# OpenBook_EBookReader_Schematic.net
KiCad netlist of a schematic drawn in EAGLE
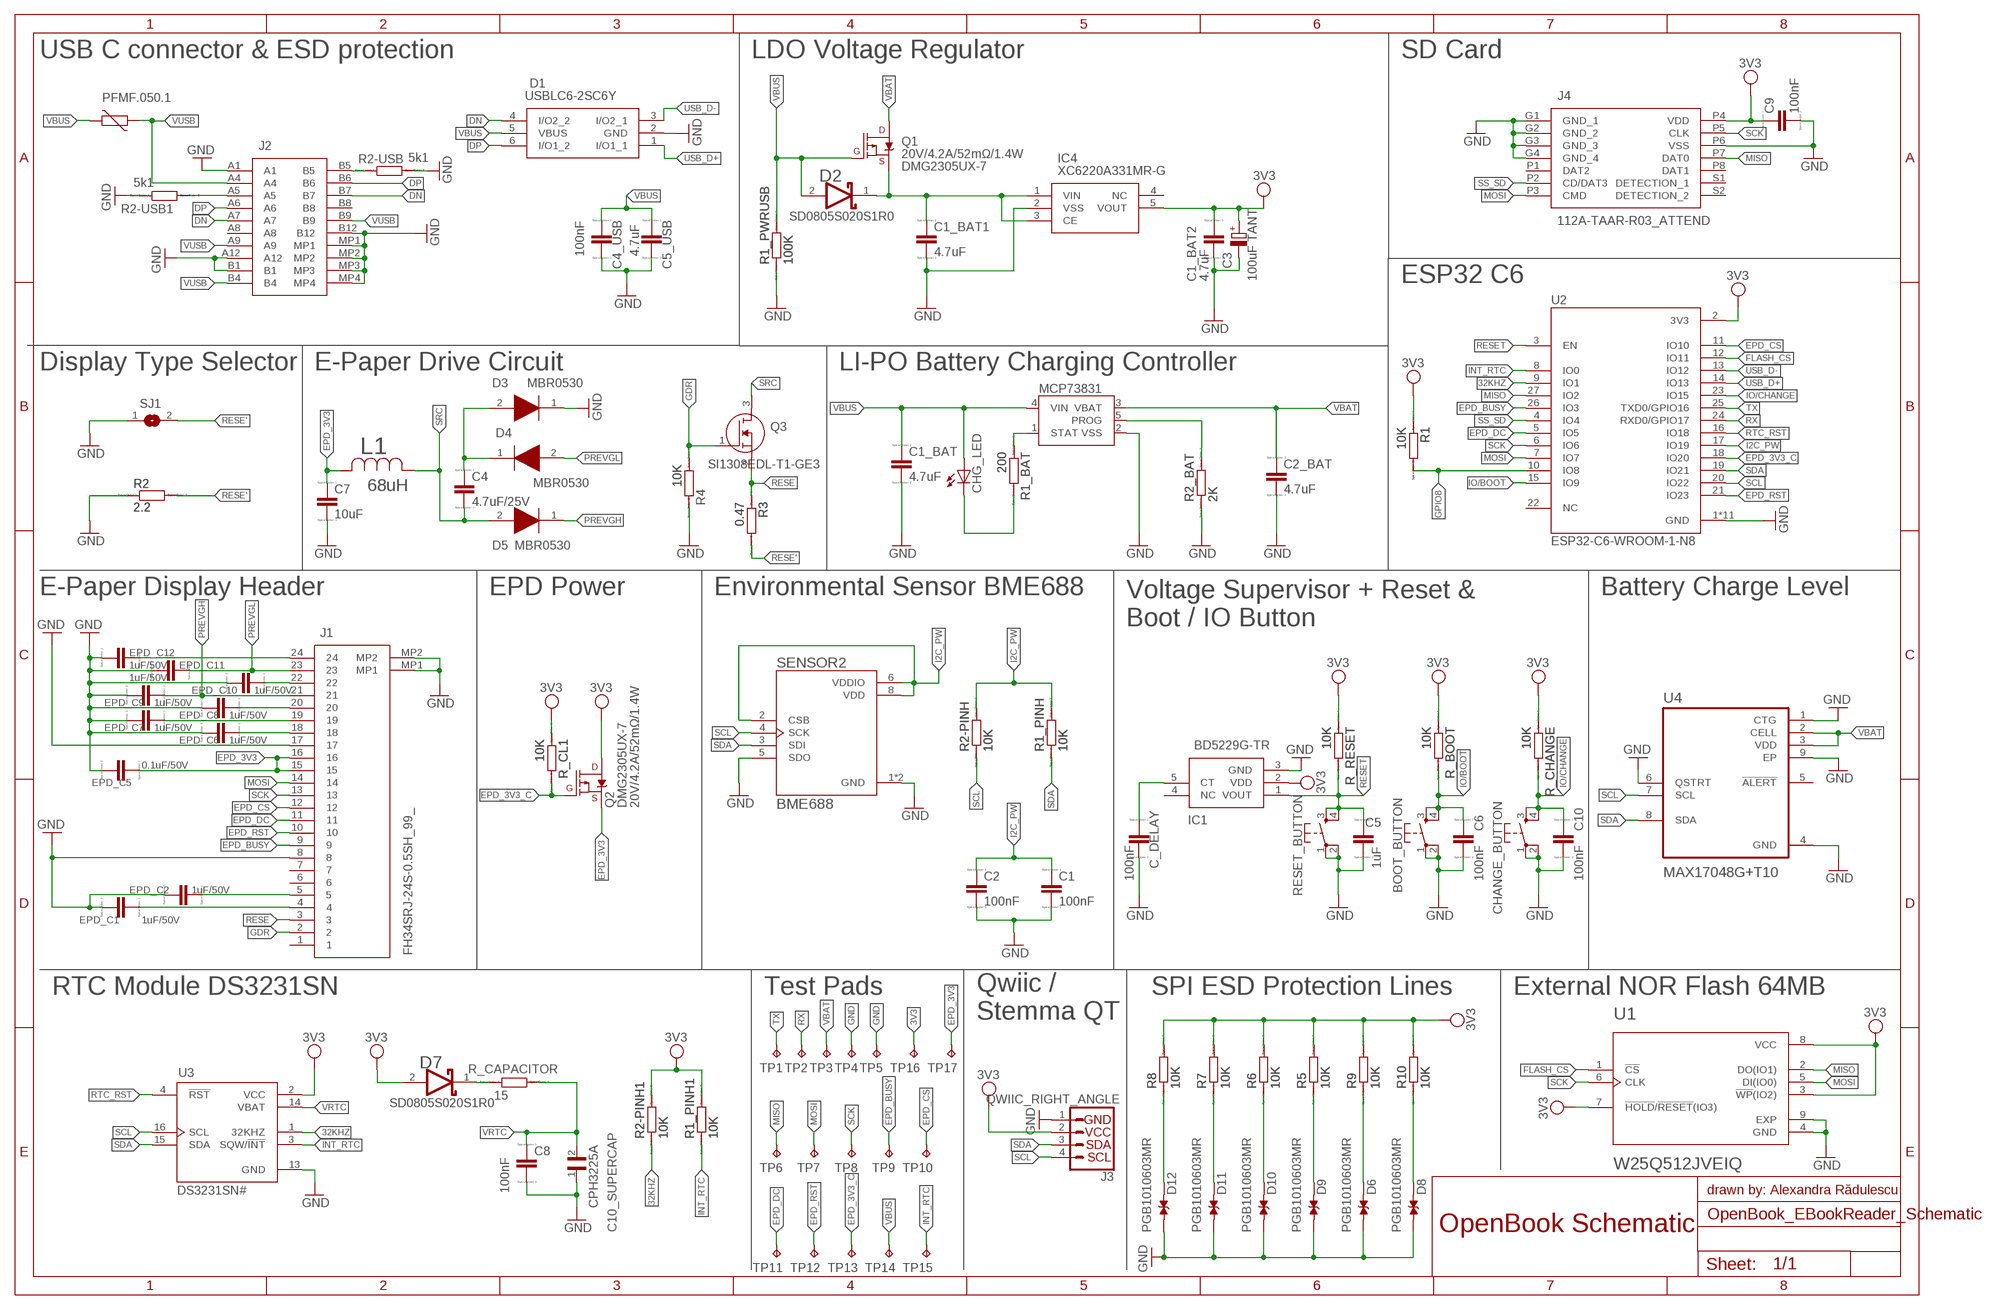
[diagram p0: schematic, sheet 1]

(export (version "E")
  (design (tool "Eeschema 10.0.6"))
  (components
    (comp (ref "BOOT_BUTTON")
      (value "BUTTON_CUSYOMV1")
      (footprint "eagle-import:MYBUTTON")
      (libsource (lib "eagle-import") (part "BUTTON_CUSYOMV1"))
    )
    (comp (ref "C1")
      (value "100nF")
      (footprint "eagle-import:ESP32_WROVER_EAGLE-LTSPICE_C0402")
      (libsource (lib "eagle-import") (part "ESP32_WROVER_EAGLE-LTSPICE_CC0402"))
    )
    (comp (ref "C1_BAT")
      (value "4.7uF")
      (footprint "eagle-import:ESP32_WROVER_EAGLE-LTSPICE_C0402")
      (libsource (lib "eagle-import") (part "ESP32_WROVER_EAGLE-LTSPICE_CC0402"))
    )
    (comp (ref "C1_BAT1")
      (value "4.7uF")
      (footprint "eagle-import:ESP32_WROVER_EAGLE-LTSPICE_C0402")
      (libsource (lib "eagle-import") (part "ESP32_WROVER_EAGLE-LTSPICE_CC0402"))
    )
    (comp (ref "C1_BAT2")
      (value "4.7uF")
      (footprint "eagle-import:ESP32_WROVER_EAGLE-LTSPICE_C0402")
      (libsource (lib "eagle-import") (part "ESP32_WROVER_EAGLE-LTSPICE_CC0402"))
    )
    (comp (ref "C2")
      (value "100nF")
      (footprint "eagle-import:ESP32_WROVER_EAGLE-LTSPICE_C0402")
      (libsource (lib "eagle-import") (part "ESP32_WROVER_EAGLE-LTSPICE_CC0402"))
    )
    (comp (ref "C2_BAT")
      (value "4.7uF")
      (footprint "eagle-import:ESP32_WROVER_EAGLE-LTSPICE_C0402")
      (libsource (lib "eagle-import") (part "ESP32_WROVER_EAGLE-LTSPICE_CC0402"))
    )
    (comp (ref "C3")
      (value "100uF TANT")
      (footprint "eagle-import:RCL_CT3528")
      (libsource (lib "eagle-import") (part "RCL_CPOL-EUCT3528"))
    )
    (comp (ref "C4")
      (value "4.7uF/25V")
      (footprint "eagle-import:ESP32_WROVER_EAGLE-LTSPICE_C0402")
      (libsource (lib "eagle-import") (part "ESP32_WROVER_EAGLE-LTSPICE_CC0402"))
    )
    (comp (ref "C4_USB")
      (value "100nF")
      (footprint "eagle-import:ESP32_WROVER_EAGLE-LTSPICE_C0402")
      (libsource (lib "eagle-import") (part "ESP32_WROVER_EAGLE-LTSPICE_CC0402"))
    )
    (comp (ref "C5")
      (value "1uF")
      (footprint "eagle-import:ESP32_WROVER_EAGLE-LTSPICE_C0402")
      (libsource (lib "eagle-import") (part "ESP32_WROVER_EAGLE-LTSPICE_CC0402"))
    )
    (comp (ref "C5_USB")
      (value "4.7uF")
      (footprint "eagle-import:ESP32_WROVER_EAGLE-LTSPICE_C0402")
      (libsource (lib "eagle-import") (part "ESP32_WROVER_EAGLE-LTSPICE_CC0402"))
    )
    (comp (ref "C6")
      (value "100nF")
      (footprint "eagle-import:ESP32_WROVER_EAGLE-LTSPICE_C0402")
      (libsource (lib "eagle-import") (part "ESP32_WROVER_EAGLE-LTSPICE_CC0402"))
    )
    (comp (ref "C7")
      (value "10uF")
      (footprint "eagle-import:ESP32_WROVER_EAGLE-LTSPICE_C0402")
      (libsource (lib "eagle-import") (part "ESP32_WROVER_EAGLE-LTSPICE_CC0402"))
    )
    (comp (ref "C8")
      (value "100nF")
      (footprint "eagle-import:ESP32_WROVER_EAGLE-LTSPICE_C0402")
      (libsource (lib "eagle-import") (part "ESP32_WROVER_EAGLE-LTSPICE_CC0402"))
    )
    (comp (ref "C9")
      (value "100nF")
      (footprint "eagle-import:ESP32_WROVER_EAGLE-LTSPICE_C0402")
      (libsource (lib "eagle-import") (part "ESP32_WROVER_EAGLE-LTSPICE_CC0402"))
    )
    (comp (ref "C10")
      (value "100nF")
      (footprint "eagle-import:ESP32_WROVER_EAGLE-LTSPICE_C0402")
      (libsource (lib "eagle-import") (part "ESP32_WROVER_EAGLE-LTSPICE_CC0402"))
    )
    (comp (ref "C10_SUPERCAP")
      (value "CPH3225A")
      (footprint "eagle-import:CAPCP3225X100N")
      (fields (field (name "MF") "Seiko Instruments"))
      (libsource (lib "eagle-import") (part "CPH3225A"))
    )
    (comp (ref "CHANGE_BUTTON")
      (value "BUTTON_CUSYOMV1")
      (footprint "eagle-import:MYBUTTON")
      (libsource (lib "eagle-import") (part "BUTTON_CUSYOMV1"))
    )
    (comp (ref "CHG_LED")
      (value "ADAFRUIT_LEDCHIP-LED0603")
      (footprint "eagle-import:ADAFRUIT_CHIP-LED0603")
      (libsource (lib "eagle-import") (part "ADAFRUIT_LEDCHIP-LED0603"))
    )
    (comp (ref "C_DELAY")
      (value "100nF")
      (footprint "eagle-import:ESP32_WROVER_EAGLE-LTSPICE_C0402")
      (libsource (lib "eagle-import") (part "ESP32_WROVER_EAGLE-LTSPICE_CC0402"))
    )
    (comp (ref "D1")
      (value "USBLC6-2SC6Y")
      (footprint "eagle-import:SOT95P280X145-6N")
      (fields (field (name "MF") "STMicroelectronics"))
      (libsource (lib "eagle-import") (part "USBLC6-2SC6Y"))
    )
    (comp (ref "D2")
      (value "ESP32_WROVER_AVX---SD0805S020S1R0_AVX_SD0805S020S1R0_0_0AVX_SD0805S020S1R0_0_0")
      (footprint "eagle-import:ESP32_WROVER_AVX---SD0805S020S1R0_AVX_SD0805S020S1R0_0")
      (fields
        (field (name "DIGIKEY_PART_NUMBER") "478-7800-1-ND")
        (field (name "MF") "AVX")
        (field (name "MOUSER_PART_NUMBER") "581-SD0805S020S1R0")
      )
      (libsource (lib "eagle-import") (part "ESP32_WROVER_AVX---SD0805S020S1R0_AVX_SD0805S020S1R0_0_0AVX_SD0805S020S1R0_0_0"))
    )
    (comp (ref "D3")
      (value "MBR0530")
      (footprint "eagle-import:SOD3716X135N")
      (fields (field (name "MF") "ON Semiconductor"))
      (libsource (lib "eagle-import") (part "MBR0530"))
    )
    (comp (ref "D4")
      (value "MBR0530")
      (footprint "eagle-import:SOD3716X135N")
      (fields (field (name "MF") "ON Semiconductor"))
      (libsource (lib "eagle-import") (part "MBR0530"))
    )
    (comp (ref "D5")
      (value "MBR0530")
      (footprint "eagle-import:SOD3716X135N")
      (fields (field (name "MF") "ON Semiconductor"))
      (libsource (lib "eagle-import") (part "MBR0530"))
    )
    (comp (ref "D6")
      (value "PGB1010603MR")
      (footprint "eagle-import:DIOC1608X36N")
      (fields (field (name "MF") "Littelfuse Inc."))
      (libsource (lib "eagle-import") (part "PGB1010603MR"))
    )
    (comp (ref "D7")
      (value "SD0805S020S1R0")
      (footprint "eagle-import:ESP32_WROVER_AVX---SD0805S020S1R0_AVX_SD0805S020S1R0_0")
      (fields
        (field (name "DIGIKEY_PART_NUMBER") "478-7800-1-ND")
        (field (name "MF") "AVX")
        (field (name "MOUSER_PART_NUMBER") "581-SD0805S020S1R0")
      )
      (libsource (lib "eagle-import") (part "ESP32_WROVER_AVX---SD0805S020S1R0_AVX_SD0805S020S1R0_0_0AVX_SD0805S020S1R0_0_0"))
    )
    (comp (ref "D8")
      (value "PGB1010603MR")
      (footprint "eagle-import:DIOC1608X36N")
      (fields (field (name "MF") "Littelfuse Inc."))
      (libsource (lib "eagle-import") (part "PGB1010603MR"))
    )
    (comp (ref "D9")
      (value "PGB1010603MR")
      (footprint "eagle-import:DIOC1608X36N")
      (fields (field (name "MF") "Littelfuse Inc."))
      (libsource (lib "eagle-import") (part "PGB1010603MR"))
    )
    (comp (ref "D10")
      (value "PGB1010603MR")
      (footprint "eagle-import:DIOC1608X36N")
      (fields (field (name "MF") "Littelfuse Inc."))
      (libsource (lib "eagle-import") (part "PGB1010603MR"))
    )
    (comp (ref "D11")
      (value "PGB1010603MR")
      (footprint "eagle-import:DIOC1608X36N")
      (fields (field (name "MF") "Littelfuse Inc."))
      (libsource (lib "eagle-import") (part "PGB1010603MR"))
    )
    (comp (ref "D12")
      (value "PGB1010603MR")
      (footprint "eagle-import:DIOC1608X36N")
      (fields (field (name "MF") "Littelfuse Inc."))
      (libsource (lib "eagle-import") (part "PGB1010603MR"))
    )
    (comp (ref "EPD_C1")
      (value "1uF/50V")
      (footprint "eagle-import:ESP32_WROVER_EAGLE-LTSPICE_C0402")
      (libsource (lib "eagle-import") (part "ESP32_WROVER_EAGLE-LTSPICE_CC0402"))
    )
    (comp (ref "EPD_C2")
      (value "1uF/50V")
      (footprint "eagle-import:ESP32_WROVER_EAGLE-LTSPICE_C0402")
      (libsource (lib "eagle-import") (part "ESP32_WROVER_EAGLE-LTSPICE_CC0402"))
    )
    (comp (ref "EPD_C5")
      (value "0.1uF/50V")
      (footprint "eagle-import:ESP32_WROVER_EAGLE-LTSPICE_C0402")
      (libsource (lib "eagle-import") (part "ESP32_WROVER_EAGLE-LTSPICE_CC0402"))
    )
    (comp (ref "EPD_C6")
      (value "1uF/50V")
      (footprint "eagle-import:ESP32_WROVER_EAGLE-LTSPICE_C0402")
      (libsource (lib "eagle-import") (part "ESP32_WROVER_EAGLE-LTSPICE_CC0402"))
    )
    (comp (ref "EPD_C7")
      (value "1uF/50V")
      (footprint "eagle-import:ESP32_WROVER_EAGLE-LTSPICE_C0402")
      (libsource (lib "eagle-import") (part "ESP32_WROVER_EAGLE-LTSPICE_CC0402"))
    )
    (comp (ref "EPD_C8")
      (value "1uF/50V")
      (footprint "eagle-import:ESP32_WROVER_EAGLE-LTSPICE_C0402")
      (libsource (lib "eagle-import") (part "ESP32_WROVER_EAGLE-LTSPICE_CC0402"))
    )
    (comp (ref "EPD_C9")
      (value "1uF/50V")
      (footprint "eagle-import:ESP32_WROVER_EAGLE-LTSPICE_C0402")
      (libsource (lib "eagle-import") (part "ESP32_WROVER_EAGLE-LTSPICE_CC0402"))
    )
    (comp (ref "EPD_C10")
      (value "1uF/50V")
      (footprint "eagle-import:ESP32_WROVER_EAGLE-LTSPICE_C0402")
      (libsource (lib "eagle-import") (part "ESP32_WROVER_EAGLE-LTSPICE_CC0402"))
    )
    (comp (ref "EPD_C11")
      (value "1uF/50V")
      (footprint "eagle-import:ESP32_WROVER_EAGLE-LTSPICE_C0402")
      (libsource (lib "eagle-import") (part "ESP32_WROVER_EAGLE-LTSPICE_CC0402"))
    )
    (comp (ref "EPD_C12")
      (value "1uF/50V")
      (footprint "eagle-import:ESP32_WROVER_EAGLE-LTSPICE_C0402")
      (libsource (lib "eagle-import") (part "ESP32_WROVER_EAGLE-LTSPICE_CC0402"))
    )
    (comp (ref "IC1")
      (value "BD5229G-TR")
      (footprint "eagle-import:SOT95P280X125-5N")
      (fields (field (name "MOUSER_PART_NUMBER") "755-BD5229G-TR"))
      (libsource (lib "eagle-import") (part "BD5229G-TR"))
    )
    (comp (ref "IC4")
      (value "XC6220A331MR-G")
      (footprint "eagle-import:SOT95P280X120-5N")
      (fields (field (name "MOUSER_PART_NUMBER") "865-XC6220A331MR-G"))
      (libsource (lib "eagle-import") (part "XC6220A331MR-G"))
    )
    (comp (ref "J1")
      (value "FH34SRJ-24S-0.5SH_99_")
      (footprint "eagle-import:FH34SRJ24S05SH99")
      (fields
        (field (name "MANUFACTURER_PART_NUMBER") "FH34SRJ-24S-0.5SH(99)")
        (field (name "MOUSER_PART_NUMBER") "798-FH34SRJ24S05SH99")
      )
      (libsource (lib "eagle-import") (part "FH34SRJ-24S-0.5SH_99_"))
    )
    (comp (ref "J2")
      (value "SAMACSYS_PARTS_USB4110-GF-A")
      (footprint "eagle-import:SAMACSYS_PARTS_USB4110GFA")
      (fields
        (field (name "MANUFACTURER_PART_NUMBER") "USB4110-GF-A")
        (field (name "MOUSER_PART_NUMBER") "640-USB4110-GF-A")
      )
      (libsource (lib "eagle-import") (part "SAMACSYS_PARTS_USB4110-GF-A"))
    )
    (comp (ref "J3")
      (value "QWIIC_RIGHT_ANGLE")
      (footprint "eagle-import:JST04_1MM_RA")
      (libsource (lib "eagle-import") (part "QWIIC_CONNECTORJS-1MM"))
    )
    (comp (ref "J4")
      (value "112A-TAAR-R03_ATTEND")
      (footprint "eagle-import:112ATAARR03ATTEND")
      (fields (field (name "MANUFACTURER_PART_NUMBER") "112A-TAAR-R03 ATTEND"))
      (libsource (lib "eagle-import") (part "112A-TAAR-R03_ATTEND"))
    )
    (comp (ref "L1")
      (value "68uH")
      (footprint "eagle-import:IND_4828-WE-TPC_WRE")
      (fields
        (field (name "MANUFACTURER_PART_NUMBER") "744043680")
        (field (name "COPYRIGHT") "Copyright (C) 2024 Ultra Librarian. All rights reserved.")
      )
      (libsource (lib "eagle-import") (part "744043680IND_4828-WE-TPC_WRE"))
    )
    (comp (ref "MCP73831")
      (value "ESP32_WROVER_SPARKFUN-IC-POWER_MCP73831")
      (footprint "eagle-import:ESP32_WROVER_SPARKFUN-IC-POWER_SOT23-5")
      (libsource (lib "eagle-import") (part "ESP32_WROVER_SPARKFUN-IC-POWER_MCP73831"))
    )
    (comp (ref "PFMF.050.1")
      (value "ESP32C6_VARISTORCN1812")
      (footprint "eagle-import:ESP32C6_VARISTOR_CT_CN1812")
      (libsource (lib "eagle-import") (part "ESP32C6_VARISTORCN1812"))
    )
    (comp (ref "Q1")
      (value "20V/4.2A/52mΩ/1.4W")
      (footprint "eagle-import:ESP32_WROVER_SPARKFUN-DISCRETESEMI_SOT23-3")
      (libsource (lib "eagle-import") (part "ESP32_WROVER_SPARKFUN-DISCRETESEMI_MOSFET_PCH-DMG2305UX-7"))
    )
    (comp (ref "Q2")
      (value "20V/4.2A/52mΩ/1.4W")
      (footprint "eagle-import:ESP32_WROVER_SPARKFUN-DISCRETESEMI_SOT23-3")
      (libsource (lib "eagle-import") (part "ESP32_WROVER_SPARKFUN-DISCRETESEMI_MOSFET_PCH-DMG2305UX-7"))
    )
    (comp (ref "Q3")
      (value "SI1308EDL-T1-GE3")
      (footprint "eagle-import:SOT65P210X110-3N")
      (fields (field (name "MF") "Vishay Siliconix"))
      (libsource (lib "eagle-import") (part "SI1308EDL-T1-GE3"))
    )
    (comp (ref "R1")
      (value "10K")
      (footprint "eagle-import:ESP32_WROVER_EAGLE-LTSPICE_R0402")
      (libsource (lib "eagle-import") (part "ESP32_WROVER_EAGLE-LTSPICE_RR0402"))
    )
    (comp (ref "R1_BAT")
      (value "200")
      (footprint "eagle-import:ESP32_WROVER_EAGLE-LTSPICE_R0402")
      (libsource (lib "eagle-import") (part "ESP32_WROVER_EAGLE-LTSPICE_RR0402"))
    )
    (comp (ref "R1_PINH")
      (value "10K")
      (footprint "eagle-import:ESP32_WROVER_EAGLE-LTSPICE_R0402")
      (libsource (lib "eagle-import") (part "ESP32_WROVER_EAGLE-LTSPICE_RR0402"))
    )
    (comp (ref "R1_PINH1")
      (value "10K")
      (footprint "eagle-import:ESP32_WROVER_EAGLE-LTSPICE_R0402")
      (libsource (lib "eagle-import") (part "ESP32_WROVER_EAGLE-LTSPICE_RR0402"))
    )
    (comp (ref "R1_PWRUSB")
      (value "100K")
      (footprint "eagle-import:ESP32_WROVER_EAGLE-LTSPICE_R0402")
      (libsource (lib "eagle-import") (part "ESP32_WROVER_EAGLE-LTSPICE_RR0402"))
    )
    (comp (ref "R2")
      (value "2.2")
      (footprint "eagle-import:ESP32_WROVER_EAGLE-LTSPICE_R0402")
      (libsource (lib "eagle-import") (part "ESP32_WROVER_EAGLE-LTSPICE_RR0402"))
    )
    (comp (ref "R2-PINH")
      (value "10K")
      (footprint "eagle-import:ESP32_WROVER_EAGLE-LTSPICE_R0402")
      (libsource (lib "eagle-import") (part "ESP32_WROVER_EAGLE-LTSPICE_RR0402"))
    )
    (comp (ref "R2-PINH1")
      (value "10K")
      (footprint "eagle-import:ESP32_WROVER_EAGLE-LTSPICE_R0402")
      (libsource (lib "eagle-import") (part "ESP32_WROVER_EAGLE-LTSPICE_RR0402"))
    )
    (comp (ref "R2-USB")
      (value "5k1")
      (footprint "eagle-import:ESP32_WROVER_EAGLE-LTSPICE_R0402")
      (libsource (lib "eagle-import") (part "ESP32_WROVER_EAGLE-LTSPICE_RR0402"))
    )
    (comp (ref "R2-USB1")
      (value "5k1")
      (footprint "eagle-import:ESP32_WROVER_EAGLE-LTSPICE_R0402")
      (libsource (lib "eagle-import") (part "ESP32_WROVER_EAGLE-LTSPICE_RR0402"))
    )
    (comp (ref "R2_BAT")
      (value "2K")
      (footprint "eagle-import:ESP32_WROVER_EAGLE-LTSPICE_R0402")
      (libsource (lib "eagle-import") (part "ESP32_WROVER_EAGLE-LTSPICE_RR0402"))
    )
    (comp (ref "R3")
      (value "0.47")
      (footprint "eagle-import:ESP32_WROVER_EAGLE-LTSPICE_R0402")
      (libsource (lib "eagle-import") (part "ESP32_WROVER_EAGLE-LTSPICE_RR0402"))
    )
    (comp (ref "R4")
      (value "10K")
      (footprint "eagle-import:ESP32_WROVER_EAGLE-LTSPICE_R0402")
      (libsource (lib "eagle-import") (part "ESP32_WROVER_EAGLE-LTSPICE_RR0402"))
    )
    (comp (ref "R5")
      (value "10K")
      (footprint "eagle-import:ESP32_WROVER_EAGLE-LTSPICE_R0402")
      (libsource (lib "eagle-import") (part "ESP32_WROVER_EAGLE-LTSPICE_RR0402"))
    )
    (comp (ref "R6")
      (value "10K")
      (footprint "eagle-import:ESP32_WROVER_EAGLE-LTSPICE_R0402")
      (libsource (lib "eagle-import") (part "ESP32_WROVER_EAGLE-LTSPICE_RR0402"))
    )
    (comp (ref "R7")
      (value "10K")
      (footprint "eagle-import:ESP32_WROVER_EAGLE-LTSPICE_R0402")
      (libsource (lib "eagle-import") (part "ESP32_WROVER_EAGLE-LTSPICE_RR0402"))
    )
    (comp (ref "R8")
      (value "10K")
      (footprint "eagle-import:ESP32_WROVER_EAGLE-LTSPICE_R0402")
      (libsource (lib "eagle-import") (part "ESP32_WROVER_EAGLE-LTSPICE_RR0402"))
    )
    (comp (ref "R9")
      (value "10K")
      (footprint "eagle-import:ESP32_WROVER_EAGLE-LTSPICE_R0402")
      (libsource (lib "eagle-import") (part "ESP32_WROVER_EAGLE-LTSPICE_RR0402"))
    )
    (comp (ref "R10")
      (value "10K")
      (footprint "eagle-import:ESP32_WROVER_EAGLE-LTSPICE_R0402")
      (libsource (lib "eagle-import") (part "ESP32_WROVER_EAGLE-LTSPICE_RR0402"))
    )
    (comp (ref "RESET_BUTTON")
      (value "BUTTON_CUSYOMV1")
      (footprint "eagle-import:MYBUTTON")
      (libsource (lib "eagle-import") (part "BUTTON_CUSYOMV1"))
    )
    (comp (ref "R_BOOT")
      (value "10K")
      (footprint "eagle-import:ESP32_WROVER_EAGLE-LTSPICE_R0402")
      (libsource (lib "eagle-import") (part "ESP32_WROVER_EAGLE-LTSPICE_RR0402"))
    )
    (comp (ref "R_CAPACITOR")
      (value "15")
      (footprint "eagle-import:ESP32_WROVER_EAGLE-LTSPICE_R0402")
      (libsource (lib "eagle-import") (part "ESP32_WROVER_EAGLE-LTSPICE_RR0402"))
    )
    (comp (ref "R_CHANGE")
      (value "10K")
      (footprint "eagle-import:ESP32_WROVER_EAGLE-LTSPICE_R0402")
      (libsource (lib "eagle-import") (part "ESP32_WROVER_EAGLE-LTSPICE_RR0402"))
    )
    (comp (ref "R_CL1")
      (value "10K")
      (footprint "eagle-import:ESP32_WROVER_EAGLE-LTSPICE_R0402")
      (libsource (lib "eagle-import") (part "ESP32_WROVER_EAGLE-LTSPICE_RR0402"))
    )
    (comp (ref "R_RESET")
      (value "10K")
      (footprint "eagle-import:ESP32_WROVER_EAGLE-LTSPICE_R0402")
      (libsource (lib "eagle-import") (part "ESP32_WROVER_EAGLE-LTSPICE_RR0402"))
    )
    (comp (ref "SENSOR2")
      (value "BME688")
      (footprint "eagle-import:ESP32_WROVER_BME680_PSON80P300X300X100-8N")
      (fields (field (name "MF") "Bosch Sensortec") (field (name "MP") "BME680"))
      (libsource (lib "eagle-import") (part "ESP32_WROVER_BME680_BME680"))
    )
    (comp (ref "SJ1") (value "SJ") (footprint "eagle-import:SJ") (libsource (lib "eagle-import") (part "SJ")))
    (comp (ref "TP1")
      (value "TPTP20R")
      (footprint "eagle-import:TP20R")
      (libsource (lib "eagle-import") (part "TPTP20R"))
    )
    (comp (ref "TP2")
      (value "TPTP20R")
      (footprint "eagle-import:TP20R")
      (libsource (lib "eagle-import") (part "TPTP20R"))
    )
    (comp (ref "TP3")
      (value "TPTP20R")
      (footprint "eagle-import:TP20R")
      (libsource (lib "eagle-import") (part "TPTP20R"))
    )
    (comp (ref "TP4")
      (value "TPTP20R")
      (footprint "eagle-import:TP20R")
      (libsource (lib "eagle-import") (part "TPTP20R"))
    )
    (comp (ref "TP5")
      (value "TPTP20R")
      (footprint "eagle-import:TP20R")
      (libsource (lib "eagle-import") (part "TPTP20R"))
    )
    (comp (ref "TP6")
      (value "TPTP20R")
      (footprint "eagle-import:TP20R")
      (libsource (lib "eagle-import") (part "TPTP20R"))
    )
    (comp (ref "TP7")
      (value "TPTP20R")
      (footprint "eagle-import:TP20R")
      (libsource (lib "eagle-import") (part "TPTP20R"))
    )
    (comp (ref "TP8")
      (value "TPTP20R")
      (footprint "eagle-import:TP20R")
      (libsource (lib "eagle-import") (part "TPTP20R"))
    )
    (comp (ref "TP9")
      (value "TPTP20R")
      (footprint "eagle-import:TP20R")
      (libsource (lib "eagle-import") (part "TPTP20R"))
    )
    (comp (ref "TP10")
      (value "TPTP20R")
      (footprint "eagle-import:TP20R")
      (libsource (lib "eagle-import") (part "TPTP20R"))
    )
    (comp (ref "TP11")
      (value "TPTP20R")
      (footprint "eagle-import:TP20R")
      (libsource (lib "eagle-import") (part "TPTP20R"))
    )
    (comp (ref "TP12")
      (value "TPTP20R")
      (footprint "eagle-import:TP20R")
      (libsource (lib "eagle-import") (part "TPTP20R"))
    )
    (comp (ref "TP13")
      (value "TPTP20R")
      (footprint "eagle-import:TP20R")
      (libsource (lib "eagle-import") (part "TPTP20R"))
    )
    (comp (ref "TP14")
      (value "TPTP20R")
      (footprint "eagle-import:TP20R")
      (libsource (lib "eagle-import") (part "TPTP20R"))
    )
    (comp (ref "TP15")
      (value "TPTP20R")
      (footprint "eagle-import:TP20R")
      (libsource (lib "eagle-import") (part "TPTP20R"))
    )
    (comp (ref "TP16")
      (value "TPTP20R")
      (footprint "eagle-import:TP20R")
      (libsource (lib "eagle-import") (part "TPTP20R"))
    )
    (comp (ref "TP17")
      (value "TPTP20R")
      (footprint "eagle-import:TP20R")
      (libsource (lib "eagle-import") (part "TPTP20R"))
    )
    (comp (ref "U1")
      (value "W25Q512JVEIQ")
      (footprint "eagle-import:SON127P600X800X80-9N")
      (fields (field (name "MF") "Winbond Electronics"))
      (libsource (lib "eagle-import") (part "W25Q512JVEIQ"))
    )
    (comp (ref "U2")
      (value "ESP32-C6-WROOM-1-N8")
      (footprint "eagle-import:XCVR_ESP32-C6-WROOM-1-N8")
      (fields (field (name "MF") "Espressif Systems"))
      (libsource (lib "eagle-import") (part "ESP32-C6-WROOM-1-N8"))
    )
    (comp (ref "U3")
      (value "DS3231SN#")
      (footprint "eagle-import:SOIC127P1032X265-16N")
      (fields (field (name "MF") "Analog Devices"))
      (libsource (lib "eagle-import") (part "DS3231SN#"))
    )
    (comp (ref "U4")
      (value "MAX17048G+T10")
      (footprint "eagle-import:SON50P200X200X80-9N")
      (fields (field (name "MF") "Analog Devices"))
      (libsource (lib "eagle-import") (part "MAX17048G+T10"))
    )
  )
  (nets
    (net (code "1") (name "3V3") (class "Default")
      (node (ref "C1_BAT2") (pin "1") (pinfunction "1_1") (pintype "passive"))
      (node (ref "C3") (pin "+") (pinfunction "+_+") (pintype "passive"))
      (node (ref "C9") (pin "1") (pinfunction "1_1") (pintype "passive"))
      (node (ref "D7") (pin "2") (pinfunction "ANODE_2") (pintype "bidirectional"))
      (node (ref "IC1") (pin "2") (pinfunction "VDD_2") (pintype "bidirectional"))
      (node (ref "IC4") (pin "5") (pinfunction "VOUT_5") (pintype "bidirectional"))
      (node (ref "J3") (pin "2") (pinfunction "2_2") (pintype "power_in"))
      (node (ref "J4") (pin "P4") (pinfunction "VDD_P4") (pintype "bidirectional"))
      (node (ref "Q2") (pin "3") (pinfunction "D_3") (pintype "bidirectional"))
      (node (ref "R1") (pin "1") (pinfunction "1_1") (pintype "passive"))
      (node (ref "R10") (pin "2") (pinfunction "2_2") (pintype "passive"))
      (node (ref "R1_PINH1") (pin "2") (pinfunction "2_2") (pintype "passive"))
      (node (ref "R2-PINH1") (pin "2") (pinfunction "2_2") (pintype "passive"))
      (node (ref "R5") (pin "2") (pinfunction "2_2") (pintype "passive"))
      (node (ref "R6") (pin "2") (pinfunction "2_2") (pintype "passive"))
      (node (ref "R7") (pin "2") (pinfunction "2_2") (pintype "passive"))
      (node (ref "R8") (pin "2") (pinfunction "2_2") (pintype "passive"))
      (node (ref "R9") (pin "2") (pinfunction "2_2") (pintype "passive"))
      (node (ref "R_BOOT") (pin "1") (pinfunction "1_1") (pintype "passive"))
      (node (ref "R_CHANGE") (pin "1") (pinfunction "1_1") (pintype "passive"))
      (node (ref "R_CL1") (pin "1") (pinfunction "1_1") (pintype "passive"))
      (node (ref "R_RESET") (pin "1") (pinfunction "1_1") (pintype "passive"))
      (node (ref "TP16") (pin "TP") (pinfunction "TP_TP") (pintype "input"))
      (node (ref "U1") (pin "3") (pinfunction "~{WP}(IO2)_3") (pintype "bidirectional"))
      (node (ref "U1") (pin "7") (pinfunction "~{HOLD}/~{RESET}(IO3)_7") (pintype "bidirectional"))
      (node (ref "U1") (pin "8") (pinfunction "VCC_8") (pintype "power_in"))
      (node (ref "U2") (pin "2") (pinfunction "3V3_2") (pintype "power_in"))
      (node (ref "U3") (pin "2") (pinfunction "VCC_2") (pintype "power_in"))
    )
    (net (code "2") (name "32KHZ") (class "Default")
      (node (ref "R2-PINH1") (pin "1") (pinfunction "1_1") (pintype "passive"))
      (node (ref "U2") (pin "9") (pinfunction "IO1_9") (pintype "bidirectional"))
      (node (ref "U3") (pin "1") (pinfunction "32KHZ_1") (pintype "output"))
    )
    (net (code "3") (name "DN") (class "Default")
      (node (ref "D1") (pin "4") (pinfunction "I/O2_2_4") (pintype "bidirectional"))
      (node (ref "J2") (pin "A7") (pinfunction "A7_A7") (pintype "bidirectional"))
      (node (ref "J2") (pin "B7") (pinfunction "B7_B7") (pintype "bidirectional"))
    )
    (net (code "4") (name "DP") (class "Default")
      (node (ref "D1") (pin "6") (pinfunction "I/O1_2_6") (pintype "bidirectional"))
      (node (ref "J2") (pin "A6") (pinfunction "A6_A6") (pintype "bidirectional"))
      (node (ref "J2") (pin "B6") (pinfunction "B6_B6") (pintype "bidirectional"))
    )
    (net (code "5") (name "EPD_3V3") (class "Default")
      (node (ref "C7") (pin "1") (pinfunction "1_1") (pintype "passive"))
      (node (ref "EPD_C5") (pin "1") (pinfunction "1_1") (pintype "passive"))
      (node (ref "J1") (pin "15") (pinfunction "15_15") (pintype "bidirectional"))
      (node (ref "J1") (pin "16") (pinfunction "16_16") (pintype "bidirectional"))
      (node (ref "L1") (pin "2") (pinfunction "2_2") (pintype "passive"))
      (node (ref "Q2") (pin "2") (pinfunction "S_2") (pintype "bidirectional"))
      (node (ref "TP17") (pin "TP") (pinfunction "TP_TP") (pintype "input"))
    )
    (net (code "6") (name "EPD_3V3_C") (class "Default")
      (node (ref "Q2") (pin "1") (pinfunction "G_1") (pintype "bidirectional"))
      (node (ref "R_CL1") (pin "2") (pinfunction "2_2") (pintype "passive"))
      (node (ref "TP13") (pin "TP") (pinfunction "TP_TP") (pintype "input"))
      (node (ref "U2") (pin "18") (pinfunction "IO20_18") (pintype "bidirectional"))
    )
    (net (code "7") (name "EPD_BUSY") (class "Default")
      (node (ref "J1") (pin "9") (pinfunction "9_9") (pintype "bidirectional"))
      (node (ref "TP9") (pin "TP") (pinfunction "TP_TP") (pintype "input"))
      (node (ref "U2") (pin "26") (pinfunction "IO3_26") (pintype "bidirectional"))
    )
    (net (code "8") (name "EPD_CS") (class "Default")
      (node (ref "J1") (pin "12") (pinfunction "12_12") (pintype "bidirectional"))
      (node (ref "TP10") (pin "TP") (pinfunction "TP_TP") (pintype "input"))
      (node (ref "U2") (pin "11") (pinfunction "IO10_11") (pintype "bidirectional"))
    )
    (net (code "9") (name "EPD_DC") (class "Default")
      (node (ref "J1") (pin "11") (pinfunction "11_11") (pintype "bidirectional"))
      (node (ref "TP11") (pin "TP") (pinfunction "TP_TP") (pintype "input"))
      (node (ref "U2") (pin "5") (pinfunction "IO5_5") (pintype "bidirectional"))
    )
    (net (code "10") (name "EPD_RST") (class "Default")
      (node (ref "J1") (pin "10") (pinfunction "10_10") (pintype "bidirectional"))
      (node (ref "TP12") (pin "TP") (pinfunction "TP_TP") (pintype "input"))
      (node (ref "U2") (pin "21") (pinfunction "IO23_21") (pintype "bidirectional"))
    )
    (net (code "11") (name "FLASH_CS") (class "Default")
      (node (ref "U1") (pin "1") (pinfunction "~{CS}_1") (pintype "input"))
      (node (ref "U2") (pin "12") (pinfunction "IO11_12") (pintype "bidirectional"))
    )
    (net (code "12") (name "GDR") (class "Default")
      (node (ref "J1") (pin "2") (pinfunction "2_2") (pintype "bidirectional"))
      (node (ref "Q3") (pin "1") (pinfunction "G_1") (pintype "bidirectional"))
      (node (ref "R4") (pin "1") (pinfunction "1_1") (pintype "passive"))
    )
    (net (code "13") (name "GND") (class "Default")
      (node (ref "BOOT_BUTTON") (pin "1") (pinfunction "1_1") (pintype "passive"))
      (node (ref "BOOT_BUTTON") (pin "2") (pinfunction "2_2") (pintype "passive"))
      (node (ref "C1") (pin "2") (pinfunction "2_2") (pintype "passive"))
      (node (ref "C10") (pin "2") (pinfunction "2_2") (pintype "passive"))
      (node (ref "C10_SUPERCAP") (pin "1") (pinfunction "1_1") (pintype "passive"))
      (node (ref "C1_BAT") (pin "2") (pinfunction "2_2") (pintype "passive"))
      (node (ref "C1_BAT1") (pin "2") (pinfunction "2_2") (pintype "passive"))
      (node (ref "C1_BAT2") (pin "2") (pinfunction "2_2") (pintype "passive"))
      (node (ref "C2") (pin "2") (pinfunction "2_2") (pintype "passive"))
      (node (ref "C2_BAT") (pin "2") (pinfunction "2_2") (pintype "passive"))
      (node (ref "C3") (pin "-") (pinfunction "-_-") (pintype "passive"))
      (node (ref "C4_USB") (pin "2") (pinfunction "2_2") (pintype "passive"))
      (node (ref "C5") (pin "2") (pinfunction "2_2") (pintype "passive"))
      (node (ref "C5_USB") (pin "2") (pinfunction "2_2") (pintype "passive"))
      (node (ref "C6") (pin "2") (pinfunction "2_2") (pintype "passive"))
      (node (ref "C7") (pin "2") (pinfunction "2_2") (pintype "passive"))
      (node (ref "C8") (pin "2") (pinfunction "2_2") (pintype "passive"))
      (node (ref "C9") (pin "2") (pinfunction "2_2") (pintype "passive"))
      (node (ref "CHANGE_BUTTON") (pin "1") (pinfunction "1_1") (pintype "passive"))
      (node (ref "CHANGE_BUTTON") (pin "2") (pinfunction "2_2") (pintype "passive"))
      (node (ref "C_DELAY") (pin "2") (pinfunction "2_2") (pintype "passive"))
      (node (ref "D1") (pin "2") (pinfunction "GND_2") (pintype "bidirectional"))
      (node (ref "D10") (pin "1") (pinfunction "1_1") (pintype "passive"))
      (node (ref "D11") (pin "1") (pinfunction "1_1") (pintype "passive"))
      (node (ref "D12") (pin "1") (pinfunction "1_1") (pintype "passive"))
      (node (ref "D3") (pin "1") (pinfunction "K_1") (pintype "bidirectional"))
      (node (ref "D6") (pin "1") (pinfunction "1_1") (pintype "passive"))
      (node (ref "D8") (pin "1") (pinfunction "1_1") (pintype "passive"))
      (node (ref "D9") (pin "1") (pinfunction "1_1") (pintype "passive"))
      (node (ref "EPD_C1") (pin "2") (pinfunction "2_2") (pintype "passive"))
      (node (ref "EPD_C10") (pin "2") (pinfunction "2_2") (pintype "passive"))
      (node (ref "EPD_C11") (pin "2") (pinfunction "2_2") (pintype "passive"))
      (node (ref "EPD_C12") (pin "2") (pinfunction "2_2") (pintype "passive"))
      (node (ref "EPD_C2") (pin "2") (pinfunction "2_2") (pintype "passive"))
      (node (ref "EPD_C5") (pin "2") (pinfunction "2_2") (pintype "passive"))
      (node (ref "EPD_C6") (pin "2") (pinfunction "2_2") (pintype "passive"))
      (node (ref "EPD_C7") (pin "2") (pinfunction "2_2") (pintype "passive"))
      (node (ref "EPD_C8") (pin "2") (pinfunction "2_2") (pintype "passive"))
      (node (ref "EPD_C9") (pin "2") (pinfunction "2_2") (pintype "passive"))
      (node (ref "IC1") (pin "3") (pinfunction "GND_3") (pintype "bidirectional"))
      (node (ref "IC4") (pin "2") (pinfunction "VSS_2") (pintype "bidirectional"))
      (node (ref "J1") (pin "17") (pinfunction "17_17") (pintype "bidirectional"))
      (node (ref "J1") (pin "8") (pinfunction "8_8") (pintype "bidirectional"))
      (node (ref "J1") (pin "MP1") (pinfunction "MP1_MP1") (pintype "bidirectional"))
      (node (ref "J1") (pin "MP2") (pinfunction "MP2_MP2") (pintype "bidirectional"))
      (node (ref "J2") (pin "A1") (pinfunction "A1_A1") (pintype "bidirectional"))
      (node (ref "J2") (pin "A12") (pinfunction "A12_A12") (pintype "bidirectional"))
      (node (ref "J2") (pin "B1") (pinfunction "B1_B1") (pintype "bidirectional"))
      (node (ref "J2") (pin "B12") (pinfunction "B12_B12") (pintype "bidirectional"))
      (node (ref "J2") (pin "MP1") (pinfunction "MP1_MP1") (pintype "bidirectional"))
      (node (ref "J2") (pin "MP2") (pinfunction "MP2_MP2") (pintype "bidirectional"))
      (node (ref "J2") (pin "MP3") (pinfunction "MP3_MP3") (pintype "bidirectional"))
      (node (ref "J2") (pin "MP4") (pinfunction "MP4_MP4") (pintype "bidirectional"))
      (node (ref "J3") (pin "1") (pinfunction "1_1") (pintype "power_in"))
      (node (ref "J4") (pin "G1") (pinfunction "GND_1_G1") (pintype "bidirectional"))
      (node (ref "J4") (pin "G2") (pinfunction "GND_2_G2") (pintype "bidirectional"))
      (node (ref "J4") (pin "G3") (pinfunction "GND_3_G3") (pintype "bidirectional"))
      (node (ref "J4") (pin "G4") (pinfunction "GND_4_G4") (pintype "bidirectional"))
      (node (ref "J4") (pin "P6") (pinfunction "VSS_P6") (pintype "bidirectional"))
      (node (ref "MCP73831") (pin "2") (pinfunction "VSS_2") (pintype "power_in"))
      (node (ref "R1_PWRUSB") (pin "1") (pinfunction "1_1") (pintype "passive"))
      (node (ref "R2") (pin "1") (pinfunction "1_1") (pintype "passive"))
      (node (ref "R2-USB") (pin "2") (pinfunction "2_2") (pintype "passive"))
      (node (ref "R2-USB1") (pin "1") (pinfunction "1_1") (pintype "passive"))
      (node (ref "R2_BAT") (pin "1") (pinfunction "1_1") (pintype "passive"))
      (node (ref "R4") (pin "2") (pinfunction "2_2") (pintype "passive"))
      (node (ref "RESET_BUTTON") (pin "1") (pinfunction "1_1") (pintype "passive"))
      (node (ref "RESET_BUTTON") (pin "2") (pinfunction "2_2") (pintype "passive"))
      (node (ref "SENSOR2") (pin "1") (pinfunction "GND_1") (pintype "power_in"))
      (node (ref "SENSOR2") (pin "5") (pinfunction "SDO_5") (pintype "bidirectional"))
      (node (ref "SENSOR2") (pin "7") (pinfunction "GND_7") (pintype "power_in"))
      (node (ref "SJ1") (pin "1") (pinfunction "1_1") (pintype "passive"))
      (node (ref "TP4") (pin "TP") (pinfunction "TP_TP") (pintype "input"))
      (node (ref "TP5") (pin "TP") (pinfunction "TP_TP") (pintype "input"))
      (node (ref "U1") (pin "4") (pinfunction "GND_4") (pintype "power_in"))
      (node (ref "U1") (pin "9") (pinfunction "EXP_9") (pintype "passive"))
      (node (ref "U2") (pin "1") (pinfunction "GND_1") (pintype "power_in"))
      (node (ref "U2") (pin "28") (pinfunction "GND_28") (pintype "power_in"))
      (node (ref "U2") (pin "29_1") (pinfunction "GND_29_1") (pintype "power_in"))
      (node (ref "U2") (pin "29_2") (pinfunction "GND_29_2") (pintype "power_in"))
      (node (ref "U2") (pin "29_3") (pinfunction "GND_29_3") (pintype "power_in"))
      (node (ref "U2") (pin "29_4") (pinfunction "GND_29_4") (pintype "power_in"))
      (node (ref "U2") (pin "29_5") (pinfunction "GND_29_5") (pintype "power_in"))
      (node (ref "U2") (pin "29_6") (pinfunction "GND_29_6") (pintype "power_in"))
      (node (ref "U2") (pin "29_7") (pinfunction "GND_29_7") (pintype "power_in"))
      (node (ref "U2") (pin "29_8") (pinfunction "GND_29_8") (pintype "power_in"))
      (node (ref "U2") (pin "29_9") (pinfunction "GND_29_9") (pintype "power_in"))
      (node (ref "U3") (pin "13") (pinfunction "GND_13") (pintype "power_in"))
      (node (ref "U4") (pin "1") (pinfunction "CTG_1") (pintype "power_in"))
      (node (ref "U4") (pin "4") (pinfunction "GND_4") (pintype "power_in"))
      (node (ref "U4") (pin "6") (pinfunction "QSTRT_6") (pintype "input"))
      (node (ref "U4") (pin "9") (pinfunction "EP_9") (pintype "power_in"))
    )
    (net (code "14") (name "GPIO8") (class "Default")
      (node (ref "R1") (pin "2") (pinfunction "2_2") (pintype "passive"))
      (node (ref "U2") (pin "10") (pinfunction "IO8_10") (pintype "bidirectional"))
    )
    (net (code "15") (name "I2C_PW") (class "Default")
      (node (ref "C1") (pin "1") (pinfunction "1_1") (pintype "passive"))
      (node (ref "C2") (pin "1") (pinfunction "1_1") (pintype "passive"))
      (node (ref "R1_PINH") (pin "2") (pinfunction "2_2") (pintype "passive"))
      (node (ref "R2-PINH") (pin "2") (pinfunction "2_2") (pintype "passive"))
      (node (ref "SENSOR2") (pin "2") (pinfunction "CSB_2") (pintype "input"))
      (node (ref "SENSOR2") (pin "6") (pinfunction "VDDIO_6") (pintype "power_in"))
      (node (ref "SENSOR2") (pin "8") (pinfunction "VDD_8") (pintype "power_in"))
      (node (ref "U2") (pin "17") (pinfunction "IO19_17") (pintype "bidirectional"))
    )
    (net (code "16") (name "INT_RTC") (class "Default")
      (node (ref "R1_PINH1") (pin "1") (pinfunction "1_1") (pintype "passive"))
      (node (ref "TP15") (pin "TP") (pinfunction "TP_TP") (pintype "input"))
      (node (ref "U2") (pin "8") (pinfunction "IO0_8") (pintype "bidirectional"))
      (node (ref "U3") (pin "3") (pinfunction "SQW/~{INT}_3") (pintype "output"))
    )
    (net (code "17") (name "IO{slash}BOOT") (class "Default")
      (node (ref "BOOT_BUTTON") (pin "3") (pinfunction "3_3") (pintype "passive"))
      (node (ref "BOOT_BUTTON") (pin "4") (pinfunction "4_4") (pintype "passive"))
      (node (ref "C6") (pin "1") (pinfunction "1_1") (pintype "passive"))
      (node (ref "R_BOOT") (pin "2") (pinfunction "2_2") (pintype "passive"))
      (node (ref "U2") (pin "15") (pinfunction "IO9_15") (pintype "bidirectional"))
    )
    (net (code "18") (name "IO{slash}CHANGE") (class "Default")
      (node (ref "C10") (pin "1") (pinfunction "1_1") (pintype "passive"))
      (node (ref "CHANGE_BUTTON") (pin "3") (pinfunction "3_3") (pintype "passive"))
      (node (ref "CHANGE_BUTTON") (pin "4") (pinfunction "4_4") (pintype "passive"))
      (node (ref "R_CHANGE") (pin "2") (pinfunction "2_2") (pintype "passive"))
      (node (ref "U2") (pin "23") (pinfunction "IO15_23") (pintype "bidirectional"))
    )
    (net (code "19") (name "MISO") (class "Default")
      (node (ref "J4") (pin "P7") (pinfunction "DAT0_P7") (pintype "bidirectional"))
      (node (ref "TP6") (pin "TP") (pinfunction "TP_TP") (pintype "input"))
      (node (ref "U1") (pin "2") (pinfunction "DO(IO1)_2") (pintype "bidirectional"))
      (node (ref "U2") (pin "27") (pinfunction "IO2_27") (pintype "bidirectional"))
    )
    (net (code "20") (name "MOSI") (class "Default")
      (node (ref "J1") (pin "14") (pinfunction "14_14") (pintype "bidirectional"))
      (node (ref "J4") (pin "P3") (pinfunction "CMD_P3") (pintype "bidirectional"))
      (node (ref "TP7") (pin "TP") (pinfunction "TP_TP") (pintype "input"))
      (node (ref "U1") (pin "5") (pinfunction "DI(IO0)_5") (pintype "bidirectional"))
      (node (ref "U2") (pin "7") (pinfunction "IO7_7") (pintype "bidirectional"))
    )
    (net (code "21") (name "Net-(CHG_LED-PadC)") (class "Default")
      (node (ref "CHG_LED") (pin "C") (pinfunction "C_C") (pintype "passive"))
      (node (ref "R1_BAT") (pin "2") (pinfunction "2_2") (pintype "passive"))
    )
    (net (code "22") (name "Net-(D2-CATHODE)") (class "Default")
      (node (ref "C1_BAT1") (pin "1") (pinfunction "1_1") (pintype "passive"))
      (node (ref "D2") (pin "1") (pinfunction "CATHODE_1") (pintype "bidirectional"))
      (node (ref "IC4") (pin "1") (pinfunction "VIN_1") (pintype "bidirectional"))
      (node (ref "IC4") (pin "3") (pinfunction "CE_3") (pintype "bidirectional"))
      (node (ref "Q1") (pin "2") (pinfunction "S_2") (pintype "bidirectional"))
    )
    (net (code "23") (name "Net-(D3-A)") (class "Default")
      (node (ref "C4") (pin "1") (pinfunction "1_1") (pintype "passive"))
      (node (ref "D3") (pin "2") (pinfunction "A_2") (pintype "bidirectional"))
      (node (ref "D4") (pin "1") (pinfunction "K_1") (pintype "bidirectional"))
    )
    (net (code "24") (name "Net-(D6-Pad2)") (class "Default")
      (node (ref "D6") (pin "2") (pinfunction "2_2") (pintype "passive"))
      (node (ref "R9") (pin "1") (pinfunction "1_1") (pintype "passive"))
    )
    (net (code "25") (name "Net-(D7-CATHODE)") (class "Default")
      (node (ref "D7") (pin "1") (pinfunction "CATHODE_1") (pintype "bidirectional"))
      (node (ref "R_CAPACITOR") (pin "2") (pinfunction "2_2") (pintype "passive"))
    )
    (net (code "26") (name "Net-(D8-Pad2)") (class "Default")
      (node (ref "D8") (pin "2") (pinfunction "2_2") (pintype "passive"))
      (node (ref "R10") (pin "1") (pinfunction "1_1") (pintype "passive"))
    )
    (net (code "27") (name "Net-(D9-Pad2)") (class "Default")
      (node (ref "D9") (pin "2") (pinfunction "2_2") (pintype "passive"))
      (node (ref "R5") (pin "1") (pinfunction "1_1") (pintype "passive"))
    )
    (net (code "28") (name "Net-(D10-Pad2)") (class "Default")
      (node (ref "D10") (pin "2") (pinfunction "2_2") (pintype "passive"))
      (node (ref "R6") (pin "1") (pinfunction "1_1") (pintype "passive"))
    )
    (net (code "29") (name "Net-(D11-Pad2)") (class "Default")
      (node (ref "D11") (pin "2") (pinfunction "2_2") (pintype "passive"))
      (node (ref "R7") (pin "1") (pinfunction "1_1") (pintype "passive"))
    )
    (net (code "30") (name "Net-(D12-Pad2)") (class "Default")
      (node (ref "D12") (pin "2") (pinfunction "2_2") (pintype "passive"))
      (node (ref "R8") (pin "1") (pinfunction "1_1") (pintype "passive"))
    )
    (net (code "31") (name "Net-(EPD_C1-Pad1)") (class "Default")
      (node (ref "EPD_C1") (pin "1") (pinfunction "1_1") (pintype "passive"))
      (node (ref "J1") (pin "4") (pinfunction "4_4") (pintype "bidirectional"))
    )
    (net (code "32") (name "Net-(EPD_C2-Pad1)") (class "Default")
      (node (ref "EPD_C2") (pin "1") (pinfunction "1_1") (pintype "passive"))
      (node (ref "J1") (pin "5") (pinfunction "5_5") (pintype "bidirectional"))
    )
    (net (code "33") (name "Net-(EPD_C6-Pad1)") (class "Default")
      (node (ref "EPD_C6") (pin "1") (pinfunction "1_1") (pintype "passive"))
      (node (ref "J1") (pin "18") (pinfunction "18_18") (pintype "bidirectional"))
    )
    (net (code "34") (name "Net-(EPD_C7-Pad1)") (class "Default")
      (node (ref "EPD_C7") (pin "1") (pinfunction "1_1") (pintype "passive"))
      (node (ref "J1") (pin "19") (pinfunction "19_19") (pintype "bidirectional"))
    )
    (net (code "35") (name "Net-(EPD_C8-Pad1)") (class "Default")
      (node (ref "EPD_C8") (pin "1") (pinfunction "1_1") (pintype "passive"))
      (node (ref "J1") (pin "20") (pinfunction "20_20") (pintype "bidirectional"))
    )
    (net (code "36") (name "Net-(EPD_C10-Pad1)") (class "Default")
      (node (ref "EPD_C10") (pin "1") (pinfunction "1_1") (pintype "passive"))
      (node (ref "J1") (pin "22") (pinfunction "22_22") (pintype "bidirectional"))
    )
    (net (code "37") (name "Net-(EPD_C12-Pad1)") (class "Default")
      (node (ref "EPD_C12") (pin "1") (pinfunction "1_1") (pintype "passive"))
      (node (ref "J1") (pin "24") (pinfunction "24_24") (pintype "bidirectional"))
    )
    (net (code "38") (name "Net-(IC1-CT)") (class "Default")
      (node (ref "C_DELAY") (pin "1") (pinfunction "1_1") (pintype "passive"))
      (node (ref "IC1") (pin "5") (pinfunction "CT_5") (pintype "bidirectional"))
    )
    (net (code "39") (name "Net-(J2-PadA5)") (class "Default")
      (node (ref "J2") (pin "A5") (pinfunction "A5_A5") (pintype "bidirectional"))
      (node (ref "R2-USB1") (pin "2") (pinfunction "2_2") (pintype "passive"))
    )
    (net (code "40") (name "Net-(J2-PadB5)") (class "Default")
      (node (ref "J2") (pin "B5") (pinfunction "B5_B5") (pintype "bidirectional"))
      (node (ref "R2-USB") (pin "1") (pinfunction "1_1") (pintype "passive"))
    )
    (net (code "41") (name "Net-(MCP73831-PROG)") (class "Default")
      (node (ref "MCP73831") (pin "5") (pinfunction "PROG_5") (pintype "input"))
      (node (ref "R2_BAT") (pin "2") (pinfunction "2_2") (pintype "passive"))
    )
    (net (code "42") (name "Net-(MCP73831-STAT)") (class "Default")
      (node (ref "MCP73831") (pin "1") (pinfunction "STAT_1") (pintype "output"))
      (node (ref "R1_BAT") (pin "1") (pinfunction "1_1") (pintype "passive"))
    )
    (net (code "43") (name "PREVGH") (class "Default")
      (node (ref "D5") (pin "1") (pinfunction "K_1") (pintype "bidirectional"))
      (node (ref "EPD_C9") (pin "1") (pinfunction "1_1") (pintype "passive"))
      (node (ref "J1") (pin "21") (pinfunction "21_21") (pintype "bidirectional"))
    )
    (net (code "44") (name "PREVGL") (class "Default")
      (node (ref "D4") (pin "2") (pinfunction "A_2") (pintype "bidirectional"))
      (node (ref "EPD_C11") (pin "1") (pinfunction "1_1") (pintype "passive"))
      (node (ref "J1") (pin "23") (pinfunction "23_23") (pintype "bidirectional"))
    )
    (net (code "45") (name "RESE") (class "Default")
      (node (ref "J1") (pin "3") (pinfunction "3_3") (pintype "bidirectional"))
      (node (ref "Q3") (pin "2") (pinfunction "S_2") (pintype "bidirectional"))
      (node (ref "R3") (pin "1") (pinfunction "1_1") (pintype "passive"))
    )
    (net (code "46") (name "RESE'") (class "Default")
      (node (ref "R2") (pin "2") (pinfunction "2_2") (pintype "passive"))
      (node (ref "R3") (pin "2") (pinfunction "2_2") (pintype "passive"))
      (node (ref "SJ1") (pin "2") (pinfunction "2_2") (pintype "passive"))
    )
    (net (code "47") (name "RESET") (class "Default")
      (node (ref "C5") (pin "1") (pinfunction "1_1") (pintype "passive"))
      (node (ref "IC1") (pin "1") (pinfunction "VOUT_1") (pintype "bidirectional"))
      (node (ref "RESET_BUTTON") (pin "3") (pinfunction "3_3") (pintype "passive"))
      (node (ref "RESET_BUTTON") (pin "4") (pinfunction "4_4") (pintype "passive"))
      (node (ref "R_RESET") (pin "2") (pinfunction "2_2") (pintype "passive"))
      (node (ref "U2") (pin "3") (pinfunction "EN_3") (pintype "input"))
    )
    (net (code "48") (name "RTC_RST") (class "Default")
      (node (ref "U2") (pin "16") (pinfunction "IO18_16") (pintype "bidirectional"))
      (node (ref "U3") (pin "4") (pinfunction "~{RST}_4") (pintype "input"))
    )
    (net (code "49") (name "RX") (class "Default")
      (node (ref "TP2") (pin "TP") (pinfunction "TP_TP") (pintype "input"))
      (node (ref "U2") (pin "24") (pinfunction "RXD0/GPIO17_24") (pintype "bidirectional"))
    )
    (net (code "50") (name "SCK") (class "Default")
      (node (ref "J1") (pin "13") (pinfunction "13_13") (pintype "bidirectional"))
      (node (ref "J4") (pin "P5") (pinfunction "CLK_P5") (pintype "bidirectional"))
      (node (ref "TP8") (pin "TP") (pinfunction "TP_TP") (pintype "input"))
      (node (ref "U1") (pin "6") (pinfunction "CLK_6") (pintype "input"))
      (node (ref "U2") (pin "6") (pinfunction "IO6_6") (pintype "bidirectional"))
    )
    (net (code "51") (name "SCL") (class "Default")
      (node (ref "J3") (pin "4") (pinfunction "4_4") (pintype "passive"))
      (node (ref "R2-PINH") (pin "1") (pinfunction "1_1") (pintype "passive"))
      (node (ref "SENSOR2") (pin "4") (pinfunction "SCK_4") (pintype "input"))
      (node (ref "U2") (pin "20") (pinfunction "IO22_20") (pintype "bidirectional"))
      (node (ref "U3") (pin "16") (pinfunction "SCL_16") (pintype "input"))
      (node (ref "U4") (pin "7") (pinfunction "SCL_7") (pintype "input"))
    )
    (net (code "52") (name "SDA") (class "Default")
      (node (ref "J3") (pin "3") (pinfunction "3_3") (pintype "passive"))
      (node (ref "R1_PINH") (pin "1") (pinfunction "1_1") (pintype "passive"))
      (node (ref "SENSOR2") (pin "3") (pinfunction "SDI_3") (pintype "bidirectional"))
      (node (ref "U2") (pin "19") (pinfunction "IO21_19") (pintype "bidirectional"))
      (node (ref "U3") (pin "15") (pinfunction "SDA_15") (pintype "bidirectional"))
      (node (ref "U4") (pin "8") (pinfunction "SDA_8") (pintype "bidirectional"))
    )
    (net (code "53") (name "SRC") (class "Default")
      (node (ref "C4") (pin "2") (pinfunction "2_2") (pintype "passive"))
      (node (ref "D5") (pin "2") (pinfunction "A_2") (pintype "bidirectional"))
      (node (ref "L1") (pin "1") (pinfunction "1_1") (pintype "passive"))
      (node (ref "Q3") (pin "3") (pinfunction "D_3") (pintype "bidirectional"))
    )
    (net (code "54") (name "SS_SD") (class "Default")
      (node (ref "J4") (pin "P2") (pinfunction "CD/DAT3_P2") (pintype "bidirectional"))
      (node (ref "U2") (pin "4") (pinfunction "IO4_4") (pintype "bidirectional"))
    )
    (net (code "55") (name "TX") (class "Default")
      (node (ref "TP1") (pin "TP") (pinfunction "TP_TP") (pintype "input"))
      (node (ref "U2") (pin "25") (pinfunction "TXD0/GPIO16_25") (pintype "bidirectional"))
    )
    (net (code "56") (name "USB_D+") (class "Default")
      (node (ref "D1") (pin "1") (pinfunction "I/O1_1_1") (pintype "bidirectional"))
      (node (ref "U2") (pin "14") (pinfunction "IO13_14") (pintype "bidirectional"))
    )
    (net (code "57") (name "USB_D-") (class "Default")
      (node (ref "D1") (pin "3") (pinfunction "I/O2_1_3") (pintype "bidirectional"))
      (node (ref "U2") (pin "13") (pinfunction "IO12_13") (pintype "bidirectional"))
    )
    (net (code "58") (name "VBAT") (class "Default")
      (node (ref "C2_BAT") (pin "1") (pinfunction "1_1") (pintype "passive"))
      (node (ref "MCP73831") (pin "3") (pinfunction "VBAT_3") (pintype "power_in"))
      (node (ref "Q1") (pin "3") (pinfunction "D_3") (pintype "bidirectional"))
      (node (ref "TP3") (pin "TP") (pinfunction "TP_TP") (pintype "input"))
      (node (ref "U4") (pin "2") (pinfunction "CELL_2") (pintype "power_in"))
      (node (ref "U4") (pin "3") (pinfunction "VDD_3") (pintype "power_in"))
    )
    (net (code "59") (name "VBUS") (class "Default")
      (node (ref "C1_BAT") (pin "1") (pinfunction "1_1") (pintype "passive"))
      (node (ref "C4_USB") (pin "1") (pinfunction "1_1") (pintype "passive"))
      (node (ref "C5_USB") (pin "1") (pinfunction "1_1") (pintype "passive"))
      (node (ref "CHG_LED") (pin "A") (pinfunction "A_A") (pintype "passive"))
      (node (ref "D1") (pin "5") (pinfunction "VBUS_5") (pintype "bidirectional"))
      (node (ref "D2") (pin "2") (pinfunction "ANODE_2") (pintype "bidirectional"))
      (node (ref "MCP73831") (pin "4") (pinfunction "VIN_4") (pintype "power_in"))
      (node (ref "PFMF.050.1") (pin "2") (pinfunction "2_2") (pintype "passive"))
      (node (ref "Q1") (pin "1") (pinfunction "G_1") (pintype "bidirectional"))
      (node (ref "R1_PWRUSB") (pin "2") (pinfunction "2_2") (pintype "passive"))
      (node (ref "TP14") (pin "TP") (pinfunction "TP_TP") (pintype "input"))
    )
    (net (code "60") (name "VRTC") (class "Default")
      (node (ref "C10_SUPERCAP") (pin "2") (pinfunction "2_2") (pintype "passive"))
      (node (ref "C8") (pin "1") (pinfunction "1_1") (pintype "passive"))
      (node (ref "R_CAPACITOR") (pin "1") (pinfunction "1_1") (pintype "passive"))
      (node (ref "U3") (pin "14") (pinfunction "VBAT_14") (pintype "power_in"))
    )
    (net (code "61") (name "VUSB") (class "Default")
      (node (ref "J2") (pin "A4") (pinfunction "A4_A4") (pintype "bidirectional"))
      (node (ref "J2") (pin "A9") (pinfunction "A9_A9") (pintype "bidirectional"))
      (node (ref "J2") (pin "B4") (pinfunction "B4_B4") (pintype "bidirectional"))
      (node (ref "J2") (pin "B9") (pinfunction "B9_B9") (pintype "bidirectional"))
      (node (ref "PFMF.050.1") (pin "1") (pinfunction "1_1") (pintype "passive"))
    )
    (net (code "62") (name "unconnected-(IC1-NC-Pad4)") (class "Default")
      (node (ref "IC1") (pin "4") (pinfunction "NC_4") (pintype "no_connect"))
    )
    (net (code "63") (name "unconnected-(IC4-NC-Pad4)") (class "Default")
      (node (ref "IC4") (pin "4") (pinfunction "NC_4") (pintype "no_connect"))
    )
    (net (code "64") (name "unconnected-(J1-Pad1)") (class "Default")
      (node (ref "J1") (pin "1") (pinfunction "1_1") (pintype "bidirectional"))
    )
    (net (code "65") (name "unconnected-(J1-Pad6)") (class "Default")
      (node (ref "J1") (pin "6") (pinfunction "6_6") (pintype "bidirectional"))
    )
    (net (code "66") (name "unconnected-(J1-Pad7)") (class "Default")
      (node (ref "J1") (pin "7") (pinfunction "7_7") (pintype "bidirectional"))
    )
    (net (code "67") (name "unconnected-(J2-PadA8)") (class "Default")
      (node (ref "J2") (pin "A8") (pinfunction "A8_A8") (pintype "bidirectional"))
    )
    (net (code "68") (name "unconnected-(J2-PadB8)") (class "Default")
      (node (ref "J2") (pin "B8") (pinfunction "B8_B8") (pintype "bidirectional"))
    )
    (net (code "69") (name "unconnected-(J4-DAT1-PadP8)") (class "Default")
      (node (ref "J4") (pin "P8") (pinfunction "DAT1_P8") (pintype "bidirectional"))
    )
    (net (code "70") (name "unconnected-(J4-DAT2-PadP1)") (class "Default")
      (node (ref "J4") (pin "P1") (pinfunction "DAT2_P1") (pintype "bidirectional"))
    )
    (net (code "71") (name "unconnected-(J4-DETECTION_1-PadS1)") (class "Default")
      (node (ref "J4") (pin "S1") (pinfunction "DETECTION_1_S1") (pintype "bidirectional"))
    )
    (net (code "72") (name "unconnected-(J4-DETECTION_2-PadS2)") (class "Default")
      (node (ref "J4") (pin "S2") (pinfunction "DETECTION_2_S2") (pintype "bidirectional"))
    )
    (net (code "73") (name "unconnected-(U2-NC-Pad22)") (class "Default")
      (node (ref "U2") (pin "22") (pinfunction "NC_22") (pintype "no_connect"))
    )
    (net (code "74") (name "unconnected-(U4-~{ALERT}-Pad5)") (class "Default")
      (node (ref "U4") (pin "5") (pinfunction "~{ALERT}_5") (pintype "output"))
    )
  )
)
